# SW_PanelGuide.net
KiCad netlist of a schematic drawn in EAGLE
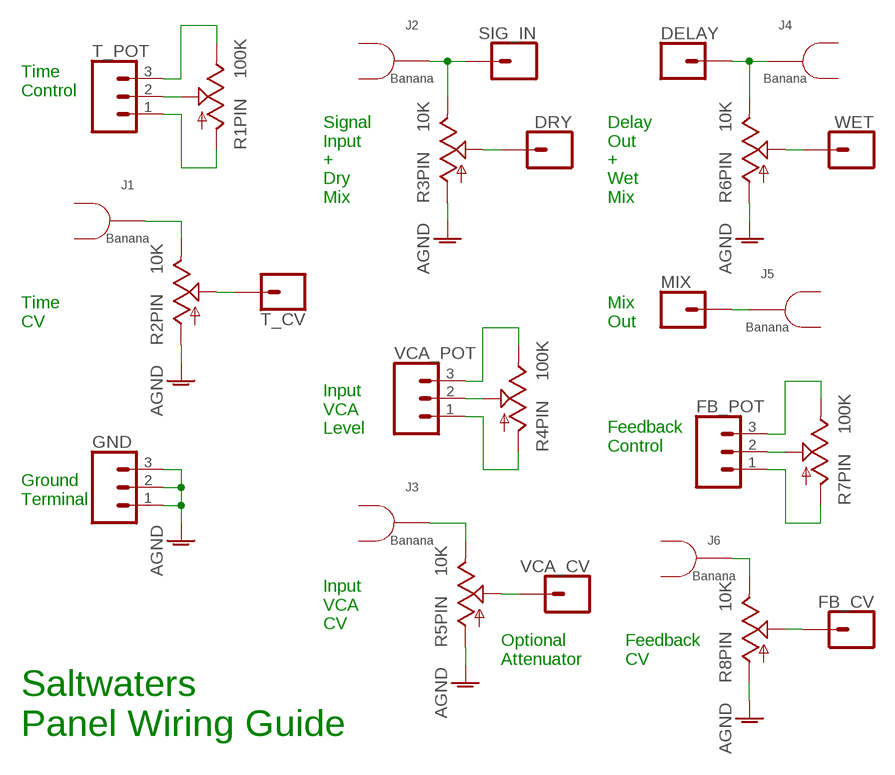
[diagram p0: schematic, sheet 1]

(export (version "E")
  (design (tool "Eeschema 10.0.6"))
  (components
    (comp (ref "DELAY")
      (value "1XWIREPAD")
      (footprint "eagle-import:1X01")
      (libsource (lib "eagle-import") (part "1XWIREPAD"))
    )
    (comp (ref "DRY")
      (value "1XWIREPAD")
      (footprint "eagle-import:1X01")
      (libsource (lib "eagle-import") (part "1XWIREPAD"))
    )
    (comp (ref "FB_CV")
      (value "1XWIREPAD")
      (footprint "eagle-import:1X01")
      (libsource (lib "eagle-import") (part "1XWIREPAD"))
    )
    (comp (ref "FB_POT")
      (value "3XWIREPAD")
      (footprint "eagle-import:1X03")
      (libsource (lib "eagle-import") (part "3XWIREPAD"))
    )
    (comp (ref "GND")
      (value "3XWIREPAD")
      (footprint "eagle-import:1X03")
      (libsource (lib "eagle-import") (part "3XWIREPAD"))
    )
    (comp (ref "J1")
      (value "BANANA_SOCKET_PAD")
      (footprint "eagle-import:BANANA_PCB_PAD")
      (libsource (lib "eagle-import") (part "BANANA_SOCKET_PAD"))
    )
    (comp (ref "J2")
      (value "BANANA_SOCKET_PAD")
      (footprint "eagle-import:BANANA_PCB_PAD")
      (libsource (lib "eagle-import") (part "BANANA_SOCKET_PAD"))
    )
    (comp (ref "J3")
      (value "BANANA_SOCKET_PAD")
      (footprint "eagle-import:BANANA_PCB_PAD")
      (libsource (lib "eagle-import") (part "BANANA_SOCKET_PAD"))
    )
    (comp (ref "J4")
      (value "BANANA_SOCKET_PAD")
      (footprint "eagle-import:BANANA_PCB_PAD")
      (libsource (lib "eagle-import") (part "BANANA_SOCKET_PAD"))
    )
    (comp (ref "J5")
      (value "BANANA_SOCKET_PAD")
      (footprint "eagle-import:BANANA_PCB_PAD")
      (libsource (lib "eagle-import") (part "BANANA_SOCKET_PAD"))
    )
    (comp (ref "J6")
      (value "BANANA_SOCKET_PAD")
      (footprint "eagle-import:BANANA_PCB_PAD")
      (libsource (lib "eagle-import") (part "BANANA_SOCKET_PAD"))
    )
    (comp (ref "MIX")
      (value "1XWIREPAD")
      (footprint "eagle-import:1X01")
      (libsource (lib "eagle-import") (part "1XWIREPAD"))
    )
    (comp (ref "R1")
      (value "100K")
      (footprint "eagle-import:ALPHA_RV09_9MMPOT")
      (libsource (lib "eagle-import") (part "POTENTIOMETER"))
    )
    (comp (ref "R2")
      (value "10K")
      (footprint "eagle-import:ALPHA_RV09_9MMPOT")
      (libsource (lib "eagle-import") (part "POTENTIOMETER"))
    )
    (comp (ref "R3")
      (value "10K")
      (footprint "eagle-import:ALPHA_RV09_9MMPOT")
      (libsource (lib "eagle-import") (part "POTENTIOMETER"))
    )
    (comp (ref "R4")
      (value "100K")
      (footprint "eagle-import:ALPHA_RV09_9MMPOT")
      (libsource (lib "eagle-import") (part "POTENTIOMETER"))
    )
    (comp (ref "R5")
      (value "10K")
      (footprint "eagle-import:ALPHA_RV09_9MMPOT")
      (libsource (lib "eagle-import") (part "POTENTIOMETER"))
    )
    (comp (ref "R6")
      (value "10K")
      (footprint "eagle-import:ALPHA_RV09_9MMPOT")
      (libsource (lib "eagle-import") (part "POTENTIOMETER"))
    )
    (comp (ref "R7")
      (value "100K")
      (footprint "eagle-import:ALPHA_RV09_9MMPOT")
      (libsource (lib "eagle-import") (part "POTENTIOMETER"))
    )
    (comp (ref "R8")
      (value "10K")
      (footprint "eagle-import:ALPHA_RV09_9MMPOT")
      (libsource (lib "eagle-import") (part "POTENTIOMETER"))
    )
    (comp (ref "SIG_IN")
      (value "1XWIREPAD")
      (footprint "eagle-import:1X01")
      (libsource (lib "eagle-import") (part "1XWIREPAD"))
    )
    (comp (ref "T_CV")
      (value "1XWIREPAD")
      (footprint "eagle-import:1X01")
      (libsource (lib "eagle-import") (part "1XWIREPAD"))
    )
    (comp (ref "T_POT")
      (value "3XWIREPAD")
      (footprint "eagle-import:1X03")
      (libsource (lib "eagle-import") (part "3XWIREPAD"))
    )
    (comp (ref "VCA_CV")
      (value "1XWIREPAD")
      (footprint "eagle-import:1X01")
      (libsource (lib "eagle-import") (part "1XWIREPAD"))
    )
    (comp (ref "VCA_POT")
      (value "3XWIREPAD")
      (footprint "eagle-import:1X03")
      (libsource (lib "eagle-import") (part "3XWIREPAD"))
    )
    (comp (ref "WET")
      (value "1XWIREPAD")
      (footprint "eagle-import:1X01")
      (libsource (lib "eagle-import") (part "1XWIREPAD"))
    )
  )
  (nets
    (net (code "1") (name "AGND") (class "Default")
      (node (ref "GND") (pin "1") (pinfunction "1_1") (pintype "passive"))
      (node (ref "GND") (pin "2") (pinfunction "2_2") (pintype "passive"))
      (node (ref "GND") (pin "3") (pinfunction "3_3") (pintype "passive"))
      (node (ref "R2") (pin "C1") (pinfunction "A_C1") (pintype "passive"))
      (node (ref "R3") (pin "C1") (pinfunction "A_C1") (pintype "passive"))
      (node (ref "R5") (pin "C1") (pinfunction "A_C1") (pintype "passive"))
      (node (ref "R6") (pin "C1") (pinfunction "A_C1") (pintype "passive"))
      (node (ref "R8") (pin "C1") (pinfunction "A_C1") (pintype "passive"))
    )
    (net (code "2") (name "Net-(J1-P$1)") (class "Default")
      (node (ref "J1") (pin "P$2") (pinfunction "P$1_P$2") (pintype "bidirectional"))
      (node (ref "R2") (pin "C3") (pinfunction "B_C3") (pintype "passive"))
    )
    (net (code "3") (name "Net-(J2-P$1)") (class "Default")
      (node (ref "J2") (pin "P$2") (pinfunction "P$1_P$2") (pintype "bidirectional"))
      (node (ref "R3") (pin "C3") (pinfunction "B_C3") (pintype "passive"))
      (node (ref "SIG_IN") (pin "1") (pinfunction "1_1") (pintype "passive"))
    )
    (net (code "4") (name "Net-(J3-P$1)") (class "Default")
      (node (ref "J3") (pin "P$2") (pinfunction "P$1_P$2") (pintype "bidirectional"))
      (node (ref "R5") (pin "C3") (pinfunction "B_C3") (pintype "passive"))
    )
    (net (code "5") (name "Net-(J4-P$1)") (class "Default")
      (node (ref "DELAY") (pin "1") (pinfunction "1_1") (pintype "passive"))
      (node (ref "J4") (pin "P$2") (pinfunction "P$1_P$2") (pintype "bidirectional"))
      (node (ref "R6") (pin "C3") (pinfunction "B_C3") (pintype "passive"))
    )
    (net (code "6") (name "Net-(J5-P$1)") (class "Default")
      (node (ref "J5") (pin "P$2") (pinfunction "P$1_P$2") (pintype "bidirectional"))
      (node (ref "MIX") (pin "1") (pinfunction "1_1") (pintype "passive"))
    )
    (net (code "7") (name "Net-(J6-P$1)") (class "Default")
      (node (ref "J6") (pin "P$2") (pinfunction "P$1_P$2") (pintype "bidirectional"))
      (node (ref "R8") (pin "C3") (pinfunction "B_C3") (pintype "passive"))
    )
    (net (code "8") (name "Net-(R1B-A)") (class "Default")
      (node (ref "R1") (pin "C1") (pinfunction "A_C1") (pintype "passive"))
      (node (ref "T_POT") (pin "1") (pinfunction "1_1") (pintype "passive"))
    )
    (net (code "9") (name "Net-(R1B-B)") (class "Default")
      (node (ref "R1") (pin "C3") (pinfunction "B_C3") (pintype "passive"))
      (node (ref "T_POT") (pin "3") (pinfunction "3_3") (pintype "passive"))
    )
    (net (code "10") (name "Net-(R1B-W)") (class "Default")
      (node (ref "R1") (pin "C2") (pinfunction "W_C2") (pintype "passive"))
      (node (ref "T_POT") (pin "2") (pinfunction "2_2") (pintype "passive"))
    )
    (net (code "11") (name "Net-(R2B-W)") (class "Default")
      (node (ref "R2") (pin "C2") (pinfunction "W_C2") (pintype "passive"))
      (node (ref "T_CV") (pin "1") (pinfunction "1_1") (pintype "passive"))
    )
    (net (code "12") (name "Net-(R3B-W)") (class "Default")
      (node (ref "DRY") (pin "1") (pinfunction "1_1") (pintype "passive"))
      (node (ref "R3") (pin "C2") (pinfunction "W_C2") (pintype "passive"))
    )
    (net (code "13") (name "Net-(R4B-A)") (class "Default")
      (node (ref "R4") (pin "C1") (pinfunction "A_C1") (pintype "passive"))
      (node (ref "VCA_POT") (pin "1") (pinfunction "1_1") (pintype "passive"))
    )
    (net (code "14") (name "Net-(R4B-B)") (class "Default")
      (node (ref "R4") (pin "C3") (pinfunction "B_C3") (pintype "passive"))
      (node (ref "VCA_POT") (pin "3") (pinfunction "3_3") (pintype "passive"))
    )
    (net (code "15") (name "Net-(R4B-W)") (class "Default")
      (node (ref "R4") (pin "C2") (pinfunction "W_C2") (pintype "passive"))
      (node (ref "VCA_POT") (pin "2") (pinfunction "2_2") (pintype "passive"))
    )
    (net (code "16") (name "Net-(R5B-W)") (class "Default")
      (node (ref "R5") (pin "C2") (pinfunction "W_C2") (pintype "passive"))
      (node (ref "VCA_CV") (pin "1") (pinfunction "1_1") (pintype "passive"))
    )
    (net (code "17") (name "Net-(R6B-W)") (class "Default")
      (node (ref "R6") (pin "C2") (pinfunction "W_C2") (pintype "passive"))
      (node (ref "WET") (pin "1") (pinfunction "1_1") (pintype "passive"))
    )
    (net (code "18") (name "Net-(R7B-A)") (class "Default")
      (node (ref "FB_POT") (pin "1") (pinfunction "1_1") (pintype "passive"))
      (node (ref "R7") (pin "C1") (pinfunction "A_C1") (pintype "passive"))
    )
    (net (code "19") (name "Net-(R7B-B)") (class "Default")
      (node (ref "FB_POT") (pin "3") (pinfunction "3_3") (pintype "passive"))
      (node (ref "R7") (pin "C3") (pinfunction "B_C3") (pintype "passive"))
    )
    (net (code "20") (name "Net-(R7B-W)") (class "Default")
      (node (ref "FB_POT") (pin "2") (pinfunction "2_2") (pintype "passive"))
      (node (ref "R7") (pin "C2") (pinfunction "W_C2") (pintype "passive"))
    )
    (net (code "21") (name "Net-(R8B-W)") (class "Default")
      (node (ref "FB_CV") (pin "1") (pinfunction "1_1") (pintype "passive"))
      (node (ref "R8") (pin "C2") (pinfunction "W_C2") (pintype "passive"))
    )
  )
)
